# Center_Console_-_IO_Expander.net
KiCad netlist of a schematic drawn in Altium Designer
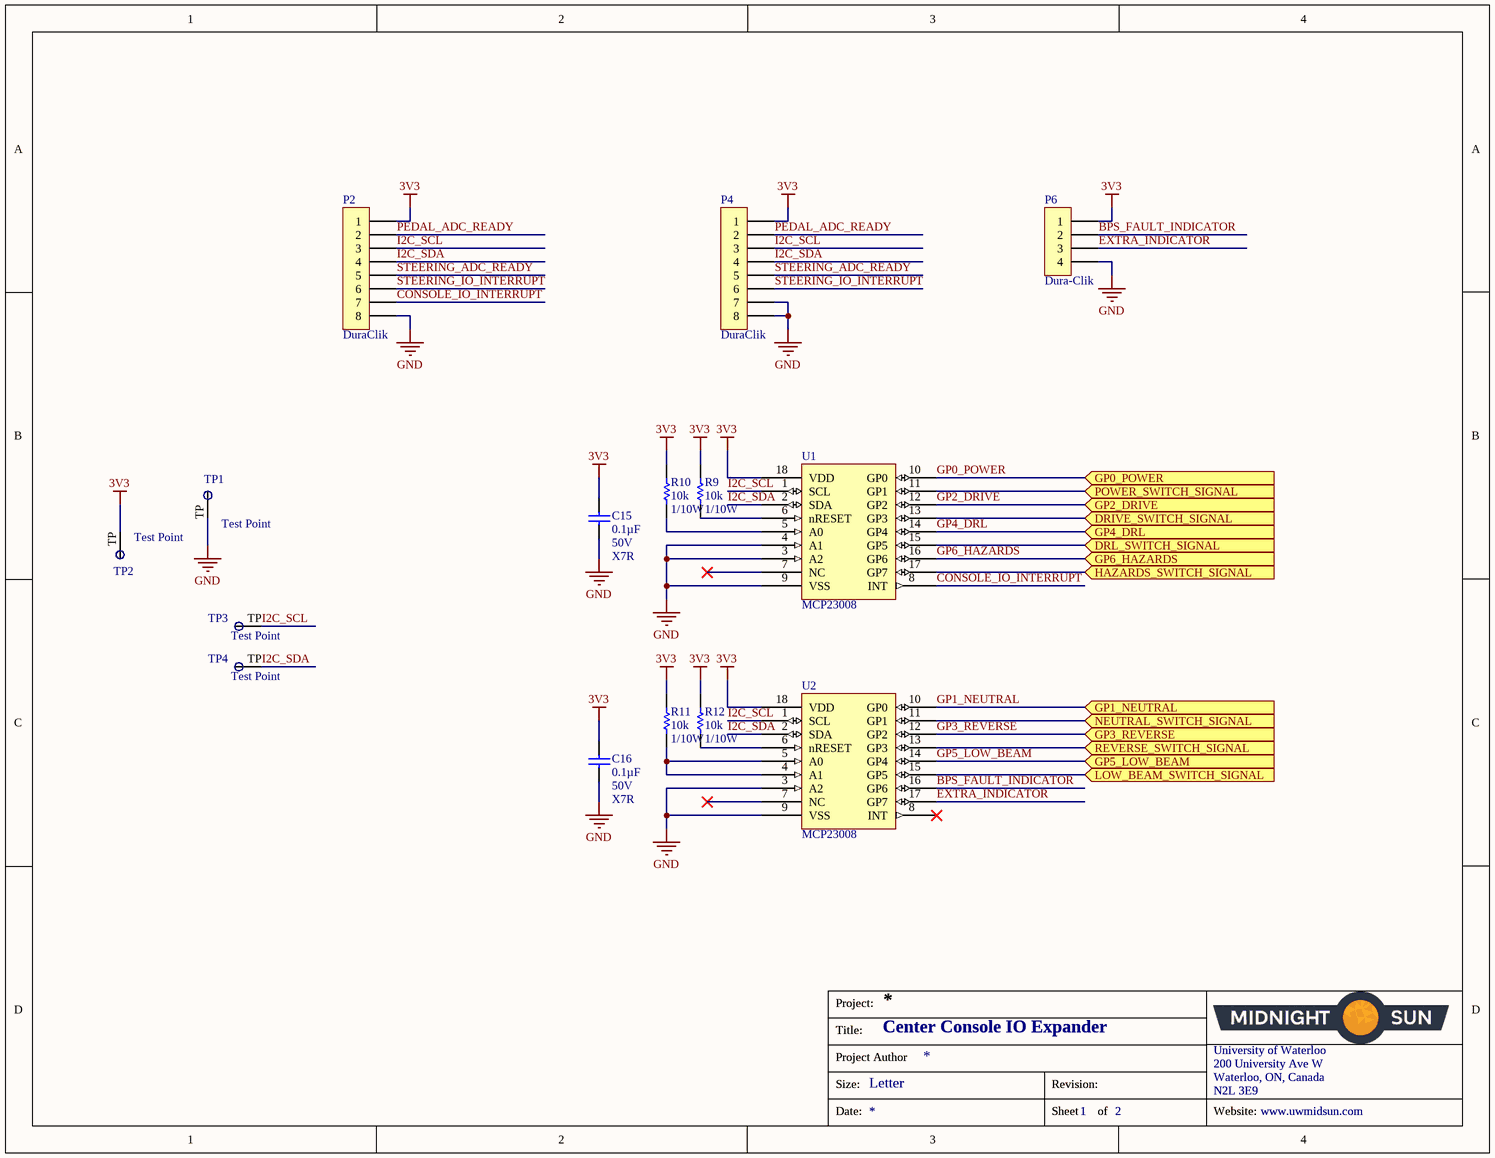
[diagram p0: Center Console - IO Expander.SchDoc]

(export (version "E")
  (design (tool "Eeschema 10.0.6"))
  (components
    (comp (ref "C15")
      (value "CAP CER 0.1UF 50V 10% X7R 0603")
      (footprint "CAP, 0603")
      (description "0.10µF ±10% 50V Ceramic Capacitor X7R 0603 (1608 Metric)")
      (fields
        (field (name "TOLERANCE") "±10%")
        (field (name "CAPACITANCE") "0.1µF")
        (field (name "VOLTAGE") "50V")
        (field (name "TEMPERATURE COEFFICIENT") "X7R")
      )
      (libsource (lib "Schematic Diagrams") (part "CAP CER 0.1UF 50V 10% X7R 0603"))
    )
    (comp (ref "C16")
      (value "CAP CER 0.1UF 50V 10% X7R 0603")
      (footprint "CAP, 0603")
      (description "0.10µF ±10% 50V Ceramic Capacitor X7R 0603 (1608 Metric)")
      (fields
        (field (name "TOLERANCE") "±10%")
        (field (name "CAPACITANCE") "0.1µF")
        (field (name "VOLTAGE") "50V")
        (field (name "TEMPERATURE COEFFICIENT") "X7R")
      )
      (libsource (lib "Schematic Diagrams") (part "CAP CER 0.1UF 50V 10% X7R 0603"))
    )
    (comp (ref "P2")
      (value "CONN 8POS DURA-CLIK 0.079\"")
      (footprint "CONN, 8POS Dura-Clik")
      (description "8 Positions Header Connector 0.079\" (2.00mm) Surface Mount Tin")
      (fields (field (name "SERIES") "DuraClik"))
      (libsource (lib "Schematic Diagrams") (part "CONN 8POS DURA-CLIK 0.079{dblquote}"))
    )
    (comp (ref "P4")
      (value "CONN 8POS DURA-CLIK 0.079\"")
      (footprint "CONN, 8POS Dura-Clik")
      (description "8 Positions Header Connector 0.079\" (2.00mm) Surface Mount Tin")
      (fields (field (name "SERIES") "DuraClik"))
      (libsource (lib "Schematic Diagrams") (part "CONN 8POS DURA-CLIK 0.079{dblquote}"))
    )
    (comp (ref "P6")
      (value "Dura-Clik")
      (footprint "CONN, 4POS DURA-CLIK VERT")
      (description "4 Positions Header Connector 0.079\" (2.00mm) Surface Mount Tin")
      (fields
        (field (name "MANUFACTURER") "Molex, LLC")
        (field (name "MANUFACTURER PART NUMBER") "5600200420")
      )
      (libsource (lib "Schematic Diagrams") (part "CONN 4POS DURA-CLIK 0.079{dblquote}"))
    )
    (comp (ref "R9")
      (value "RES 10K OHM 1% 1/10W 0603")
      (footprint "RES, 0603")
      (description "RES SMD 10K OHM 1% 1/10W 0603")
      (fields
        (field (name "TOLERANCE") "±1%")
        (field (name "RESISTANCE") "10k")
        (field (name "POWER") "1/10W")
      )
      (libsource (lib "Schematic Diagrams") (part "RES 10K OHM 1% 1/10W 0603"))
    )
    (comp (ref "R10")
      (value "RES 10K OHM 1% 1/10W 0603")
      (footprint "RES, 0603")
      (description "RES SMD 10K OHM 1% 1/10W 0603")
      (fields
        (field (name "TOLERANCE") "±1%")
        (field (name "RESISTANCE") "10k")
        (field (name "POWER") "1/10W")
      )
      (libsource (lib "Schematic Diagrams") (part "RES 10K OHM 1% 1/10W 0603"))
    )
    (comp (ref "R11")
      (value "RES 10K OHM 1% 1/10W 0603")
      (footprint "RES, 0603")
      (description "RES SMD 10K OHM 1% 1/10W 0603")
      (fields
        (field (name "TOLERANCE") "±1%")
        (field (name "RESISTANCE") "10k")
        (field (name "POWER") "1/10W")
      )
      (libsource (lib "Schematic Diagrams") (part "RES 10K OHM 1% 1/10W 0603"))
    )
    (comp (ref "R12")
      (value "RES 10K OHM 1% 1/10W 0603")
      (footprint "RES, 0603")
      (description "RES SMD 10K OHM 1% 1/10W 0603")
      (fields
        (field (name "TOLERANCE") "±1%")
        (field (name "RESISTANCE") "10k")
        (field (name "POWER") "1/10W")
      )
      (libsource (lib "Schematic Diagrams") (part "RES 10K OHM 1% 1/10W 0603"))
    )
    (comp (ref "TP1")
      (value "Test Point")
      (footprint "Test Point")
      (libsource (lib "Schematic Diagrams") (part "Test Point"))
    )
    (comp (ref "TP2")
      (value "Test Point")
      (footprint "Test Point")
      (libsource (lib "Schematic Diagrams") (part "Test Point"))
    )
    (comp (ref "TP3")
      (value "Test Point")
      (footprint "Test Point")
      (libsource (lib "Schematic Diagrams") (part "Test Point"))
    )
    (comp (ref "TP4")
      (value "Test Point")
      (footprint "Test Point")
      (libsource (lib "Schematic Diagrams") (part "Test Point"))
    )
    (comp (ref "U1")
      (value "MCP23008")
      (footprint "IC 18SOIC")
      (description "MCP23008 I/O Expander 8B+1Int 18P SOIC")
      (fields
        (field (name "MANUFACTURER") "Microchip Technology")
        (field (name "MANUFACTURER PART NUMBER") "MCP23008T-E/SO")
      )
      (libsource (lib "Schematic Diagrams") (part "IC I/O EXPANDER I2C 8B 18SOIC"))
    )
    (comp (ref "U2")
      (value "MCP23008")
      (footprint "IC 18SOIC")
      (description "MCP23008 I/O Expander 8B+1Int 18P SOIC")
      (fields
        (field (name "MANUFACTURER") "Microchip Technology")
        (field (name "MANUFACTURER PART NUMBER") "MCP23008T-E/SO")
      )
      (libsource (lib "Schematic Diagrams") (part "IC I/O EXPANDER I2C 8B 18SOIC"))
    )
  )
  (nets
    (net (code "1") (name "/BPS_FAULT_INDICATOR") (class "Default")
      (node (ref "P6") (pin "2") (pinfunction "2_2") (pintype "passive"))
      (node (ref "U2") (pin "16") (pinfunction "GP6_16") (pintype "bidirectional"))
    )
    (net (code "2") (name "/CONSOLE_IO_INTERRUPT") (class "Default")
      (node (ref "P2") (pin "7") (pinfunction "7_7") (pintype "passive"))
      (node (ref "U1") (pin "8") (pinfunction "INT_8") (pintype "output"))
    )
    (net (code "3") (name "/DRIVE_SWITCH_SIGNAL") (class "Default")
      (node (ref "U1") (pin "13") (pinfunction "GP3_13") (pintype "bidirectional"))
    )
    (net (code "4") (name "/DRL_SWITCH_SIGNAL") (class "Default")
      (node (ref "U1") (pin "15") (pinfunction "GP5_15") (pintype "bidirectional"))
    )
    (net (code "5") (name "/EXTRA_INDICATOR") (class "Default")
      (node (ref "P6") (pin "3") (pinfunction "3_3") (pintype "passive"))
      (node (ref "U2") (pin "17") (pinfunction "GP7_17") (pintype "bidirectional"))
    )
    (net (code "6") (name "/GP0_POWER") (class "Default")
      (node (ref "U1") (pin "10") (pinfunction "GP0_10") (pintype "bidirectional"))
    )
    (net (code "7") (name "/GP1_NEUTRAL") (class "Default")
      (node (ref "U2") (pin "10") (pinfunction "GP0_10") (pintype "bidirectional"))
    )
    (net (code "8") (name "/GP2_DRIVE") (class "Default")
      (node (ref "U1") (pin "12") (pinfunction "GP2_12") (pintype "bidirectional"))
    )
    (net (code "9") (name "/GP3_REVERSE") (class "Default")
      (node (ref "U2") (pin "12") (pinfunction "GP2_12") (pintype "bidirectional"))
    )
    (net (code "10") (name "/GP4_DRL") (class "Default")
      (node (ref "U1") (pin "14") (pinfunction "GP4_14") (pintype "bidirectional"))
    )
    (net (code "11") (name "/GP5_LOW_BEAM") (class "Default")
      (node (ref "U2") (pin "14") (pinfunction "GP4_14") (pintype "bidirectional"))
    )
    (net (code "12") (name "/GP6_HAZARDS") (class "Default")
      (node (ref "U1") (pin "16") (pinfunction "GP6_16") (pintype "bidirectional"))
    )
    (net (code "13") (name "/HAZARDS_SWITCH_SIGNAL") (class "Default")
      (node (ref "U1") (pin "17") (pinfunction "GP7_17") (pintype "bidirectional"))
    )
    (net (code "14") (name "/I2C_SCL") (class "Default")
      (node (ref "P2") (pin "3") (pinfunction "3_3") (pintype "passive"))
      (node (ref "P4") (pin "3") (pinfunction "3_3") (pintype "passive"))
      (node (ref "TP3") (pin "TP") (pinfunction "1_TP") (pintype "passive"))
      (node (ref "U1") (pin "1") (pinfunction "SCL_1") (pintype "bidirectional"))
      (node (ref "U2") (pin "1") (pinfunction "SCL_1") (pintype "bidirectional"))
    )
    (net (code "15") (name "/I2C_SDA") (class "Default")
      (node (ref "P2") (pin "4") (pinfunction "4_4") (pintype "passive"))
      (node (ref "P4") (pin "4") (pinfunction "4_4") (pintype "passive"))
      (node (ref "TP4") (pin "TP") (pinfunction "1_TP") (pintype "passive"))
      (node (ref "U1") (pin "2") (pinfunction "SDA_2") (pintype "bidirectional"))
      (node (ref "U2") (pin "2") (pinfunction "SDA_2") (pintype "bidirectional"))
    )
    (net (code "16") (name "/LOW_BEAM_SWITCH_SIGNAL") (class "Default")
      (node (ref "U2") (pin "15") (pinfunction "GP5_15") (pintype "bidirectional"))
    )
    (net (code "17") (name "/NEUTRAL_SWITCH_SIGNAL") (class "Default")
      (node (ref "U2") (pin "11") (pinfunction "GP1_11") (pintype "bidirectional"))
    )
    (net (code "18") (name "/PEDAL_ADC_READY") (class "Default")
      (node (ref "P2") (pin "2") (pinfunction "2_2") (pintype "passive"))
      (node (ref "P4") (pin "2") (pinfunction "2_2") (pintype "passive"))
    )
    (net (code "19") (name "/POWER_SWITCH_SIGNAL") (class "Default")
      (node (ref "U1") (pin "11") (pinfunction "GP1_11") (pintype "bidirectional"))
    )
    (net (code "20") (name "/REVERSE_SWITCH_SIGNAL") (class "Default")
      (node (ref "U2") (pin "13") (pinfunction "GP3_13") (pintype "bidirectional"))
    )
    (net (code "21") (name "/STEERING_ADC_READY") (class "Default")
      (node (ref "P2") (pin "5") (pinfunction "5_5") (pintype "passive"))
      (node (ref "P4") (pin "5") (pinfunction "5_5") (pintype "passive"))
    )
    (net (code "22") (name "/STEERING_IO_INTERRUPT") (class "Default")
      (node (ref "P2") (pin "6") (pinfunction "6_6") (pintype "passive"))
      (node (ref "P4") (pin "6") (pinfunction "6_6") (pintype "passive"))
    )
    (net (code "23") (name "3V3") (class "Default")
      (node (ref "C15") (pin "1") (pinfunction "1_1") (pintype "passive"))
      (node (ref "C16") (pin "1") (pinfunction "1_1") (pintype "passive"))
      (node (ref "P2") (pin "1") (pinfunction "1_1") (pintype "passive"))
      (node (ref "P4") (pin "1") (pinfunction "1_1") (pintype "passive"))
      (node (ref "P6") (pin "1") (pinfunction "1_1") (pintype "passive"))
      (node (ref "R10") (pin "1") (pinfunction "1_1") (pintype "passive"))
      (node (ref "R11") (pin "1") (pinfunction "1_1") (pintype "passive"))
      (node (ref "R12") (pin "1") (pinfunction "1_1") (pintype "passive"))
      (node (ref "R9") (pin "1") (pinfunction "1_1") (pintype "passive"))
      (node (ref "TP2") (pin "TP") (pinfunction "1_TP") (pintype "passive"))
      (node (ref "U1") (pin "18") (pinfunction "VDD_18") (pintype "power_in"))
      (node (ref "U2") (pin "18") (pinfunction "VDD_18") (pintype "power_in"))
    )
    (net (code "24") (name "GND") (class "Default")
      (node (ref "C15") (pin "2") (pinfunction "2_2") (pintype "passive"))
      (node (ref "C16") (pin "2") (pinfunction "2_2") (pintype "passive"))
      (node (ref "P2") (pin "8") (pinfunction "8_8") (pintype "passive"))
      (node (ref "P4") (pin "7") (pinfunction "7_7") (pintype "passive"))
      (node (ref "P4") (pin "8") (pinfunction "8_8") (pintype "passive"))
      (node (ref "P6") (pin "4") (pinfunction "4_4") (pintype "passive"))
      (node (ref "TP1") (pin "TP") (pinfunction "1_TP") (pintype "passive"))
      (node (ref "U1") (pin "3") (pinfunction "A2_3") (pintype "input"))
      (node (ref "U1") (pin "4") (pinfunction "A1_4") (pintype "input"))
      (node (ref "U1") (pin "9") (pinfunction "VSS_9") (pintype "power_in"))
      (node (ref "U2") (pin "3") (pinfunction "A2_3") (pintype "input"))
      (node (ref "U2") (pin "9") (pinfunction "VSS_9") (pintype "power_in"))
    )
    (net (code "25") (name "Net-(U1-A0)") (class "Default")
      (node (ref "R10") (pin "2") (pinfunction "2_2") (pintype "passive"))
      (node (ref "U1") (pin "5") (pinfunction "A0_5") (pintype "input"))
    )
    (net (code "26") (name "Net-(U1-nRESET)") (class "Default")
      (node (ref "R9") (pin "2") (pinfunction "2_2") (pintype "passive"))
      (node (ref "U1") (pin "6") (pinfunction "nRESET_6") (pintype "input"))
    )
    (net (code "27") (name "Net-(U2-A0)") (class "Default")
      (node (ref "R11") (pin "2") (pinfunction "2_2") (pintype "passive"))
      (node (ref "U2") (pin "4") (pinfunction "A1_4") (pintype "input"))
      (node (ref "U2") (pin "5") (pinfunction "A0_5") (pintype "input"))
    )
    (net (code "28") (name "Net-(U2-nRESET)") (class "Default")
      (node (ref "R12") (pin "2") (pinfunction "2_2") (pintype "passive"))
      (node (ref "U2") (pin "6") (pinfunction "nRESET_6") (pintype "input"))
    )
    (net (code "29") (name "unconnected-(U1-NC-Pad7)") (class "Default")
      (node (ref "U1") (pin "7") (pinfunction "NC_7") (pintype "passive+no_connect"))
    )
    (net (code "30") (name "unconnected-(U2-INT-Pad8)") (class "Default")
      (node (ref "U2") (pin "8") (pinfunction "INT_8") (pintype "output+no_connect"))
    )
    (net (code "31") (name "unconnected-(U2-NC-Pad7)") (class "Default")
      (node (ref "U2") (pin "7") (pinfunction "NC_7") (pintype "passive+no_connect"))
    )
  )
)
